# ElectroChemCC.net
KiCad netlist of a schematic drawn in EAGLE
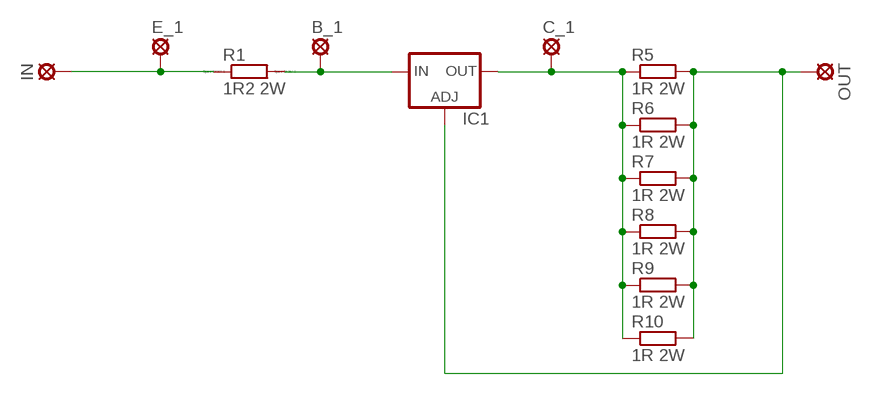
[diagram p0: schematic, sheet 1]

(export (version "E")
  (design (tool "Eeschema 10.0.6"))
  (components
    (comp (ref "B_1")
      (value "SE14")
      (footprint "eagle-import:SE14")
      (libsource (lib "eagle-import") (part "SE14"))
    )
    (comp (ref "C_1")
      (value "SE14")
      (footprint "eagle-import:SE14")
      (libsource (lib "eagle-import") (part "SE14"))
    )
    (comp (ref "E_1")
      (value "SE14")
      (footprint "eagle-import:SE14")
      (libsource (lib "eagle-import") (part "SE14"))
    )
    (comp (ref "IC1")
      (value "LM317TS")
      (footprint "eagle-import:317TS")
      (libsource (lib "eagle-import") (part "LM317TS"))
    )
    (comp (ref "IN")
      (value "SE14")
      (footprint "eagle-import:SE14")
      (libsource (lib "eagle-import") (part "SE14"))
    )
    (comp (ref "OUT")
      (value "SE14")
      (footprint "eagle-import:SE14")
      (libsource (lib "eagle-import") (part "SE14"))
    )
    (comp (ref "R1")
      (value "1R2 2W")
      (footprint "eagle-import:0207_10")
      (libsource (lib "eagle-import") (part "R0207/10"))
    )
    (comp (ref "R5")
      (value "1R 2W")
      (footprint "eagle-import:0617_22")
      (libsource (lib "eagle-import") (part "R-EU_0617/22"))
    )
    (comp (ref "R6")
      (value "1R 2W")
      (footprint "eagle-import:0617_22")
      (libsource (lib "eagle-import") (part "R-EU_0617/22"))
    )
    (comp (ref "R7")
      (value "1R 2W")
      (footprint "eagle-import:0617_22")
      (libsource (lib "eagle-import") (part "R-EU_0617/22"))
    )
    (comp (ref "R8")
      (value "1R 2W")
      (footprint "eagle-import:0617_22")
      (libsource (lib "eagle-import") (part "R-EU_0617/22"))
    )
    (comp (ref "R9")
      (value "1R 2W")
      (footprint "eagle-import:0617_22")
      (libsource (lib "eagle-import") (part "R-EU_0617/22"))
    )
    (comp (ref "R10")
      (value "1R 2W")
      (footprint "eagle-import:0617_22")
      (libsource (lib "eagle-import") (part "R-EU_0617/22"))
    )
  )
  (nets
    (net (code "1") (name "Net-(E_1-PadMP)") (class "Default")
      (node (ref "E_1") (pin "MP") (pinfunction "MP_MP") (pintype "passive"))
      (node (ref "IN") (pin "MP") (pinfunction "MP_MP") (pintype "passive"))
      (node (ref "R1") (pin "1") (pinfunction "1_1") (pintype "passive"))
    )
    (net (code "2") (name "Net-(IC1-ADJ)") (class "Default")
      (node (ref "IC1") (pin "1") (pinfunction "ADJ_1") (pintype "input"))
      (node (ref "OUT") (pin "MP") (pinfunction "MP_MP") (pintype "passive"))
      (node (ref "R10") (pin "2") (pinfunction "2_2") (pintype "passive"))
      (node (ref "R5") (pin "2") (pinfunction "2_2") (pintype "passive"))
      (node (ref "R6") (pin "2") (pinfunction "2_2") (pintype "passive"))
      (node (ref "R7") (pin "2") (pinfunction "2_2") (pintype "passive"))
      (node (ref "R8") (pin "2") (pinfunction "2_2") (pintype "passive"))
      (node (ref "R9") (pin "2") (pinfunction "2_2") (pintype "passive"))
    )
    (net (code "3") (name "Net-(IC1-IN)") (class "Default")
      (node (ref "B_1") (pin "MP") (pinfunction "MP_MP") (pintype "passive"))
      (node (ref "IC1") (pin "3") (pinfunction "IN_3") (pintype "input"))
      (node (ref "R1") (pin "2") (pinfunction "2_2") (pintype "passive"))
    )
    (net (code "4") (name "Net-(IC1-OUT)") (class "Default")
      (node (ref "C_1") (pin "MP") (pinfunction "MP_MP") (pintype "passive"))
      (node (ref "IC1") (pin "2") (pinfunction "OUT_2") (pintype "passive"))
      (node (ref "R10") (pin "1") (pinfunction "1_1") (pintype "passive"))
      (node (ref "R5") (pin "1") (pinfunction "1_1") (pintype "passive"))
      (node (ref "R6") (pin "1") (pinfunction "1_1") (pintype "passive"))
      (node (ref "R7") (pin "1") (pinfunction "1_1") (pintype "passive"))
      (node (ref "R8") (pin "1") (pinfunction "1_1") (pintype "passive"))
      (node (ref "R9") (pin "1") (pinfunction "1_1") (pintype "passive"))
    )
  )
)
